# ESP8266.net
KiCad netlist of a schematic drawn in EAGLE
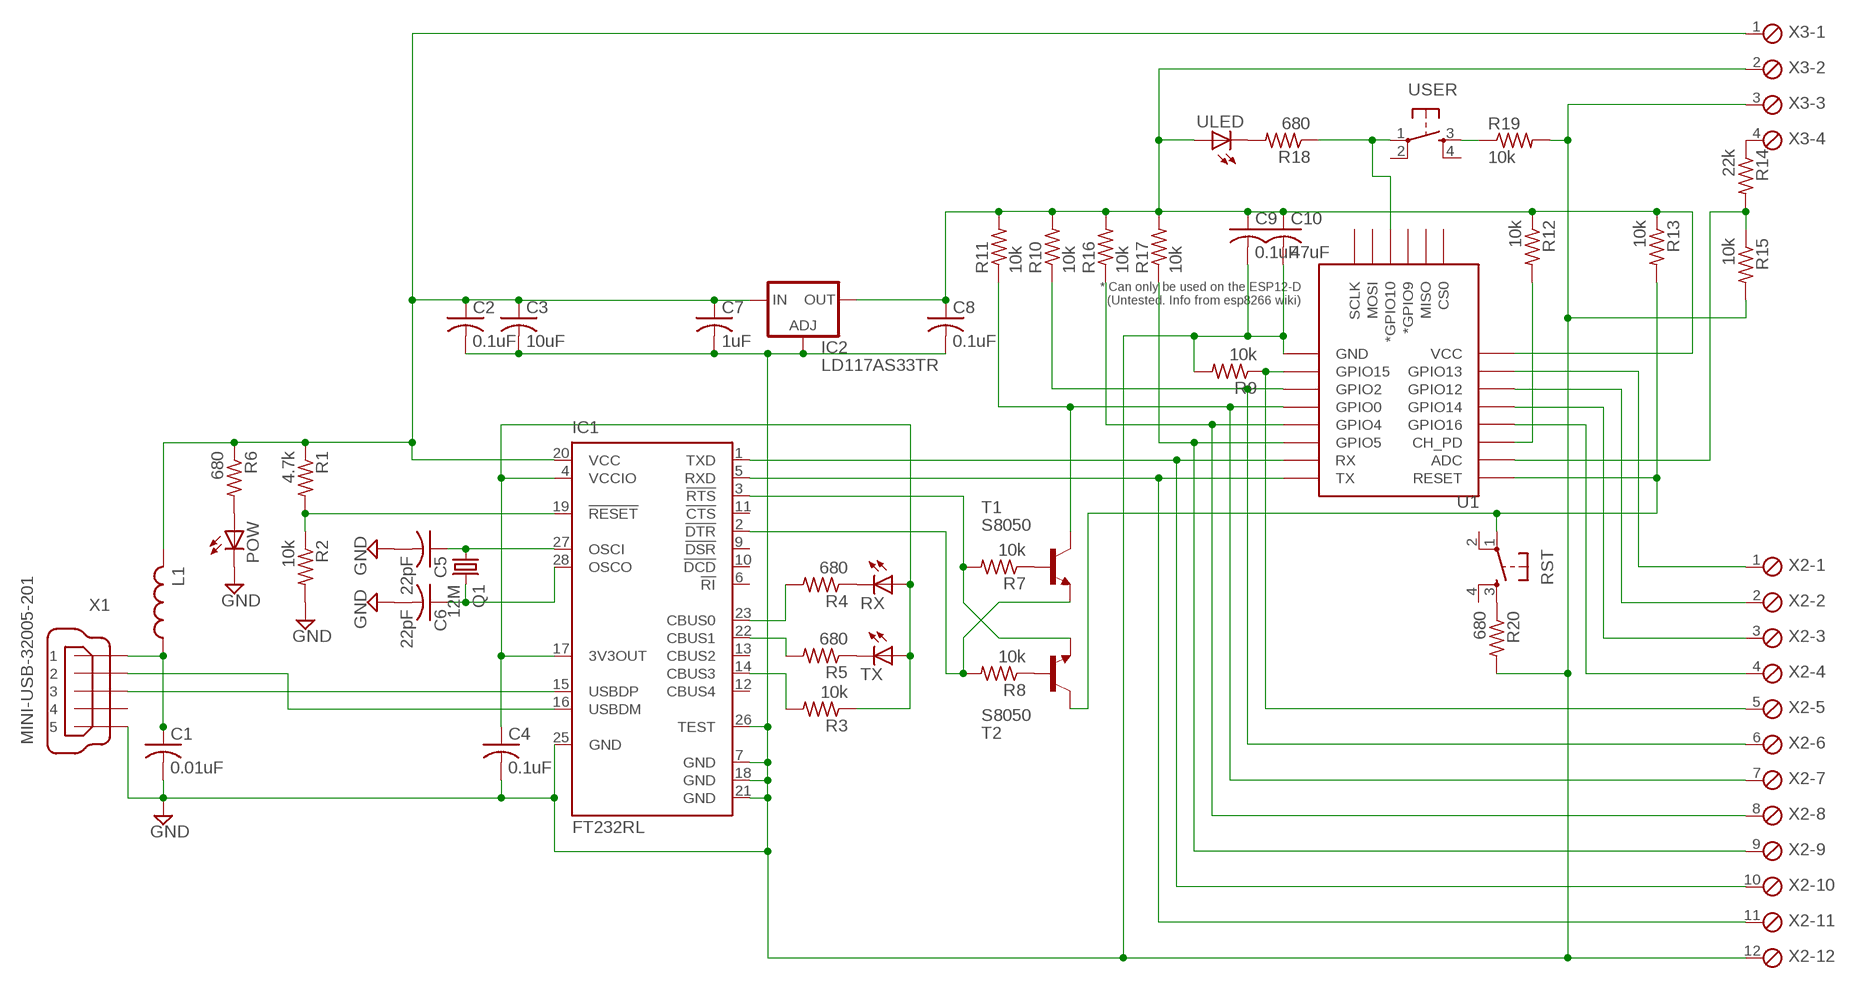
[diagram p0: schematic, sheet 1]

(export (version "E")
  (design (tool "Eeschema 10.0.6"))
  (components
    (comp (ref "C1")
      (value "0.01uF")
      (footprint "eagle-import:C0805")
      (libsource (lib "eagle-import") (part "C-USC0805"))
    )
    (comp (ref "C2")
      (value "0.1uF")
      (footprint "eagle-import:C0805")
      (libsource (lib "eagle-import") (part "C-USC0805"))
    )
    (comp (ref "C3")
      (value "10uF")
      (footprint "eagle-import:C0805")
      (libsource (lib "eagle-import") (part "C-USC0805"))
    )
    (comp (ref "C4")
      (value "0.1uF")
      (footprint "eagle-import:C0805")
      (libsource (lib "eagle-import") (part "C-USC0805"))
    )
    (comp (ref "C5")
      (value "22pF")
      (footprint "eagle-import:C0805")
      (libsource (lib "eagle-import") (part "C-USC0805"))
    )
    (comp (ref "C6")
      (value "22pF")
      (footprint "eagle-import:C0805")
      (libsource (lib "eagle-import") (part "C-USC0805"))
    )
    (comp (ref "C7")
      (value "1uF")
      (footprint "eagle-import:C0805")
      (libsource (lib "eagle-import") (part "C-USC0805"))
    )
    (comp (ref "C8")
      (value "0.1uF")
      (footprint "eagle-import:C0805")
      (libsource (lib "eagle-import") (part "C-USC0805"))
    )
    (comp (ref "C9")
      (value "0.1uF")
      (footprint "eagle-import:C0805")
      (libsource (lib "eagle-import") (part "C-USC0805"))
    )
    (comp (ref "C10")
      (value "47uF")
      (footprint "eagle-import:C0805")
      (libsource (lib "eagle-import") (part "C-USC0805"))
    )
    (comp (ref "IC1")
      (value "FT232RL")
      (footprint "eagle-import:SSOP28")
      (libsource (lib "eagle-import") (part "FT232RL"))
    )
    (comp (ref "IC2")
      (value "LD117AS33TR")
      (footprint "eagle-import:SOT223")
      (libsource (lib "eagle-import") (part "LD117A?S33TR"))
    )
    (comp (ref "L1")
      (value "L-USL2012C")
      (footprint "eagle-import:L2012C")
      (libsource (lib "eagle-import") (part "L-USL2012C"))
    )
    (comp (ref "POW")
      (value "LEDCHIP-LED0805")
      (footprint "eagle-import:CHIP-LED0805")
      (libsource (lib "eagle-import") (part "LEDCHIP-LED0805"))
    )
    (comp (ref "Q1")
      (value "12M")
      (footprint "eagle-import:SM49")
      (libsource (lib "eagle-import") (part "CRYSTALSM49"))
    )
    (comp (ref "R1")
      (value "4.7k")
      (footprint "eagle-import:R0805")
      (libsource (lib "eagle-import") (part "R-US_R0805"))
    )
    (comp (ref "R2")
      (value "10k")
      (footprint "eagle-import:R0805")
      (libsource (lib "eagle-import") (part "R-US_R0805"))
    )
    (comp (ref "R3")
      (value "10k")
      (footprint "eagle-import:R0805")
      (libsource (lib "eagle-import") (part "R-US_R0805"))
    )
    (comp (ref "R4")
      (value "680")
      (footprint "eagle-import:R0805")
      (libsource (lib "eagle-import") (part "R-US_R0805"))
    )
    (comp (ref "R5")
      (value "680")
      (footprint "eagle-import:R0805")
      (libsource (lib "eagle-import") (part "R-US_R0805"))
    )
    (comp (ref "R6")
      (value "680")
      (footprint "eagle-import:R0805")
      (libsource (lib "eagle-import") (part "R-US_R0805"))
    )
    (comp (ref "R7")
      (value "10k")
      (footprint "eagle-import:R0805")
      (libsource (lib "eagle-import") (part "R-US_R0805"))
    )
    (comp (ref "R8")
      (value "10k")
      (footprint "eagle-import:R0805")
      (libsource (lib "eagle-import") (part "R-US_R0805"))
    )
    (comp (ref "R9")
      (value "10k")
      (footprint "eagle-import:R0805")
      (libsource (lib "eagle-import") (part "R-US_R0805"))
    )
    (comp (ref "R10")
      (value "10k")
      (footprint "eagle-import:R0805")
      (libsource (lib "eagle-import") (part "R-US_R0805"))
    )
    (comp (ref "R11")
      (value "10k")
      (footprint "eagle-import:R0805")
      (libsource (lib "eagle-import") (part "R-US_R0805"))
    )
    (comp (ref "R12")
      (value "10k")
      (footprint "eagle-import:R0805")
      (libsource (lib "eagle-import") (part "R-US_R0805"))
    )
    (comp (ref "R13")
      (value "10k")
      (footprint "eagle-import:R0805")
      (libsource (lib "eagle-import") (part "R-US_R0805"))
    )
    (comp (ref "R14")
      (value "22k")
      (footprint "eagle-import:R0805")
      (libsource (lib "eagle-import") (part "R-US_R0805"))
    )
    (comp (ref "R15")
      (value "10k")
      (footprint "eagle-import:R0805")
      (libsource (lib "eagle-import") (part "R-US_R0805"))
    )
    (comp (ref "R16")
      (value "10k")
      (footprint "eagle-import:R0805")
      (libsource (lib "eagle-import") (part "R-US_R0805"))
    )
    (comp (ref "R17")
      (value "10k")
      (footprint "eagle-import:R0805")
      (libsource (lib "eagle-import") (part "R-US_R0805"))
    )
    (comp (ref "R18")
      (value "680")
      (footprint "eagle-import:R0805")
      (libsource (lib "eagle-import") (part "R-US_R0805"))
    )
    (comp (ref "R19")
      (value "10k")
      (footprint "eagle-import:R0805")
      (libsource (lib "eagle-import") (part "R-US_R0805"))
    )
    (comp (ref "R20")
      (value "680")
      (footprint "eagle-import:R0805")
      (libsource (lib "eagle-import") (part "R-US_R0805"))
    )
    (comp (ref "RST")
      (value "DTSM-6")
      (footprint "eagle-import:DTSM-6")
      (libsource (lib "eagle-import") (part "DTSM-6"))
    )
    (comp (ref "RX")
      (value "LEDCHIP-LED0805")
      (footprint "eagle-import:CHIP-LED0805")
      (libsource (lib "eagle-import") (part "LEDCHIP-LED0805"))
    )
    (comp (ref "T1")
      (value "S8050")
      (footprint "eagle-import:SOT23-EBC")
      (libsource (lib "eagle-import") (part "-NPN-SOT23-EBC"))
    )
    (comp (ref "T2")
      (value "S8050")
      (footprint "eagle-import:SOT23-EBC")
      (libsource (lib "eagle-import") (part "-NPN-SOT23-EBC"))
    )
    (comp (ref "TX")
      (value "LEDCHIP-LED0805")
      (footprint "eagle-import:CHIP-LED0805")
      (libsource (lib "eagle-import") (part "LEDCHIP-LED0805"))
    )
    (comp (ref "U1")
      (value "ESP12ESMD")
      (footprint "eagle-import:ESP12E-SMD")
      (libsource (lib "eagle-import") (part "ESP12ESMD"))
    )
    (comp (ref "ULED")
      (value "LEDCHIP-LED0805")
      (footprint "eagle-import:CHIP-LED0805")
      (libsource (lib "eagle-import") (part "LEDCHIP-LED0805"))
    )
    (comp (ref "USER")
      (value "DTSM-6")
      (footprint "eagle-import:DTSM-6")
      (libsource (lib "eagle-import") (part "DTSM-6"))
    )
    (comp (ref "X1")
      (value "MINI-USB-32005-201")
      (footprint "eagle-import:32005-201")
      (libsource (lib "eagle-import") (part "MINI-USB-32005-201"))
    )
    (comp (ref "X2")
      (value "MPT12")
      (footprint "eagle-import:12POL254")
      (libsource (lib "eagle-import") (part "MPT12"))
    )
    (comp (ref "X3")
      (value "MPT4")
      (footprint "eagle-import:4POL254")
      (libsource (lib "eagle-import") (part "MPT4"))
    )
  )
  (nets
    (net (code "1") (name "GND") (class "Default")
      (node (ref "C1") (pin "2") (pinfunction "2_2") (pintype "passive"))
      (node (ref "C10") (pin "2") (pinfunction "2_2") (pintype "passive"))
      (node (ref "C2") (pin "2") (pinfunction "2_2") (pintype "passive"))
      (node (ref "C3") (pin "2") (pinfunction "2_2") (pintype "passive"))
      (node (ref "C4") (pin "2") (pinfunction "2_2") (pintype "passive"))
      (node (ref "C5") (pin "2") (pinfunction "2_2") (pintype "passive"))
      (node (ref "C6") (pin "2") (pinfunction "2_2") (pintype "passive"))
      (node (ref "C7") (pin "2") (pinfunction "2_2") (pintype "passive"))
      (node (ref "C8") (pin "2") (pinfunction "2_2") (pintype "passive"))
      (node (ref "C9") (pin "2") (pinfunction "2_2") (pintype "passive"))
      (node (ref "IC1") (pin "18") (pinfunction "GND_18") (pintype "power_in"))
      (node (ref "IC1") (pin "21") (pinfunction "GND_21") (pintype "power_in"))
      (node (ref "IC1") (pin "25") (pinfunction "GND_25") (pintype "power_in"))
      (node (ref "IC1") (pin "26") (pinfunction "TEST_26") (pintype "input"))
      (node (ref "IC1") (pin "7") (pinfunction "GND_7") (pintype "power_in"))
      (node (ref "IC2") (pin "1") (pinfunction "ADJ_1") (pintype "input"))
      (node (ref "POW") (pin "C") (pinfunction "C_C") (pintype "passive"))
      (node (ref "R15") (pin "2") (pinfunction "2_2") (pintype "passive"))
      (node (ref "R19") (pin "2") (pinfunction "2_2") (pintype "passive"))
      (node (ref "R2") (pin "2") (pinfunction "2_2") (pintype "passive"))
      (node (ref "R20") (pin "2") (pinfunction "2_2") (pintype "passive"))
      (node (ref "R9") (pin "2") (pinfunction "2_2") (pintype "passive"))
      (node (ref "U1") (pin "GND") (pinfunction "GND_GND") (pintype "bidirectional"))
      (node (ref "X1") (pin "5") (pinfunction "5_5") (pintype "passive"))
      (node (ref "X2") (pin "12") (pinfunction "1_12") (pintype "passive"))
      (node (ref "X3") (pin "3") (pinfunction "1_3") (pintype "passive"))
    )
    (net (code "2") (name "Net-(C1-Pad1)") (class "Default")
      (node (ref "C1") (pin "1") (pinfunction "1_1") (pintype "passive"))
      (node (ref "L1") (pin "1") (pinfunction "1_1") (pintype "passive"))
      (node (ref "X1") (pin "1") (pinfunction "1_1") (pintype "passive"))
    )
    (net (code "3") (name "Net-(IC1-3V3OUT)") (class "Default")
      (node (ref "C4") (pin "1") (pinfunction "1_1") (pintype "passive"))
      (node (ref "IC1") (pin "17") (pinfunction "3V3OUT_17") (pintype "output"))
      (node (ref "IC1") (pin "4") (pinfunction "VCCIO_4") (pintype "power_in"))
      (node (ref "R3") (pin "1") (pinfunction "1_1") (pintype "passive"))
      (node (ref "RX") (pin "A") (pinfunction "A_A") (pintype "passive"))
      (node (ref "TX") (pin "A") (pinfunction "A_A") (pintype "passive"))
    )
    (net (code "4") (name "Net-(IC1-CBUS0)") (class "Default")
      (node (ref "IC1") (pin "23") (pinfunction "CBUS0_23") (pintype "bidirectional"))
      (node (ref "R4") (pin "2") (pinfunction "2_2") (pintype "passive"))
    )
    (net (code "5") (name "Net-(IC1-CBUS1)") (class "Default")
      (node (ref "IC1") (pin "22") (pinfunction "CBUS1_22") (pintype "bidirectional"))
      (node (ref "R5") (pin "2") (pinfunction "2_2") (pintype "passive"))
    )
    (net (code "6") (name "Net-(IC1-CBUS3)") (class "Default")
      (node (ref "IC1") (pin "14") (pinfunction "CBUS3_14") (pintype "bidirectional"))
      (node (ref "R3") (pin "2") (pinfunction "2_2") (pintype "passive"))
    )
    (net (code "7") (name "Net-(IC1-OSCI)") (class "Default")
      (node (ref "C5") (pin "1") (pinfunction "1_1") (pintype "passive"))
      (node (ref "IC1") (pin "27") (pinfunction "OSCI_27") (pintype "input"))
      (node (ref "Q1") (pin "1") (pinfunction "1_1") (pintype "passive"))
    )
    (net (code "8") (name "Net-(IC1-OSCO)") (class "Default")
      (node (ref "C6") (pin "1") (pinfunction "1_1") (pintype "passive"))
      (node (ref "IC1") (pin "28") (pinfunction "OSCO_28") (pintype "output"))
      (node (ref "Q1") (pin "2") (pinfunction "2_2") (pintype "passive"))
    )
    (net (code "9") (name "Net-(IC1-RXD)") (class "Default")
      (node (ref "IC1") (pin "5") (pinfunction "RXD_5") (pintype "input"))
      (node (ref "U1") (pin "TXD0") (pinfunction "TX_TXD0") (pintype "bidirectional"))
      (node (ref "X2") (pin "11") (pinfunction "1_11") (pintype "passive"))
    )
    (net (code "10") (name "Net-(IC1-TXD)") (class "Default")
      (node (ref "IC1") (pin "1") (pinfunction "TXD_1") (pintype "output"))
      (node (ref "U1") (pin "RXD0") (pinfunction "RX_RXD0") (pintype "bidirectional"))
      (node (ref "X2") (pin "10") (pinfunction "1_10") (pintype "passive"))
    )
    (net (code "11") (name "Net-(IC1-USBDM)") (class "Default")
      (node (ref "IC1") (pin "16") (pinfunction "USBDM_16") (pintype "bidirectional"))
      (node (ref "X1") (pin "2") (pinfunction "2_2") (pintype "passive"))
    )
    (net (code "12") (name "Net-(IC1-USBDP)") (class "Default")
      (node (ref "IC1") (pin "15") (pinfunction "USBDP_15") (pintype "bidirectional"))
      (node (ref "X1") (pin "3") (pinfunction "3_3") (pintype "passive"))
    )
    (net (code "13") (name "Net-(IC1-VCC)") (class "Default")
      (node (ref "C2") (pin "1") (pinfunction "1_1") (pintype "passive"))
      (node (ref "C3") (pin "1") (pinfunction "1_1") (pintype "passive"))
      (node (ref "C7") (pin "1") (pinfunction "1_1") (pintype "passive"))
      (node (ref "IC1") (pin "20") (pinfunction "VCC_20") (pintype "power_in"))
      (node (ref "IC2") (pin "3") (pinfunction "IN_3") (pintype "input"))
      (node (ref "L1") (pin "2") (pinfunction "2_2") (pintype "passive"))
      (node (ref "R1") (pin "1") (pinfunction "1_1") (pintype "passive"))
      (node (ref "R6") (pin "1") (pinfunction "1_1") (pintype "passive"))
      (node (ref "X3") (pin "1") (pinfunction "1_1") (pintype "passive"))
    )
    (net (code "14") (name "Net-(IC1-~{DTR})") (class "Default")
      (node (ref "IC1") (pin "2") (pinfunction "~{DTR}_2") (pintype "output"))
      (node (ref "R8") (pin "2") (pinfunction "2_2") (pintype "passive"))
      (node (ref "T1") (pin "E") (pinfunction "E_E") (pintype "passive"))
    )
    (net (code "15") (name "Net-(IC1-~{RESET})") (class "Default")
      (node (ref "IC1") (pin "19") (pinfunction "~{RESET}_19") (pintype "input"))
      (node (ref "R1") (pin "2") (pinfunction "2_2") (pintype "passive"))
      (node (ref "R2") (pin "1") (pinfunction "1_1") (pintype "passive"))
    )
    (net (code "16") (name "Net-(IC1-~{RTS})") (class "Default")
      (node (ref "IC1") (pin "3") (pinfunction "~{RTS}_3") (pintype "output"))
      (node (ref "R7") (pin "2") (pinfunction "2_2") (pintype "passive"))
      (node (ref "T2") (pin "E") (pinfunction "E_E") (pintype "passive"))
    )
    (net (code "17") (name "Net-(IC2-OUT)") (class "Default")
      (node (ref "C10") (pin "1") (pinfunction "1_1") (pintype "passive"))
      (node (ref "C8") (pin "1") (pinfunction "1_1") (pintype "passive"))
      (node (ref "C9") (pin "1") (pinfunction "1_1") (pintype "passive"))
      (node (ref "IC2") (pin "4") (pinfunction "OUT_4") (pintype "passive"))
      (node (ref "R10") (pin "2") (pinfunction "2_2") (pintype "passive"))
      (node (ref "R11") (pin "2") (pinfunction "2_2") (pintype "passive"))
      (node (ref "R12") (pin "1") (pinfunction "1_1") (pintype "passive"))
      (node (ref "R13") (pin "1") (pinfunction "1_1") (pintype "passive"))
      (node (ref "R16") (pin "2") (pinfunction "2_2") (pintype "passive"))
      (node (ref "R17") (pin "2") (pinfunction "2_2") (pintype "passive"))
      (node (ref "U1") (pin "VCC") (pinfunction "VCC_VCC") (pintype "bidirectional"))
      (node (ref "ULED") (pin "A") (pinfunction "A_A") (pintype "passive"))
      (node (ref "X3") (pin "2") (pinfunction "1_2") (pintype "passive"))
    )
    (net (code "18") (name "Net-(POW-PadA)") (class "Default")
      (node (ref "POW") (pin "A") (pinfunction "A_A") (pintype "passive"))
      (node (ref "R6") (pin "2") (pinfunction "2_2") (pintype "passive"))
    )
    (net (code "19") (name "Net-(R4-Pad1)") (class "Default")
      (node (ref "R4") (pin "1") (pinfunction "1_1") (pintype "passive"))
      (node (ref "RX") (pin "C") (pinfunction "C_C") (pintype "passive"))
    )
    (net (code "20") (name "Net-(R5-Pad1)") (class "Default")
      (node (ref "R5") (pin "1") (pinfunction "1_1") (pintype "passive"))
      (node (ref "TX") (pin "C") (pinfunction "C_C") (pintype "passive"))
    )
    (net (code "21") (name "Net-(R7-Pad1)") (class "Default")
      (node (ref "R7") (pin "1") (pinfunction "1_1") (pintype "passive"))
      (node (ref "T1") (pin "B") (pinfunction "B_B") (pintype "passive"))
    )
    (net (code "22") (name "Net-(R8-Pad1)") (class "Default")
      (node (ref "R8") (pin "1") (pinfunction "1_1") (pintype "passive"))
      (node (ref "T2") (pin "B") (pinfunction "B_B") (pintype "passive"))
    )
    (net (code "23") (name "Net-(R12-Pad2)") (class "Default")
      (node (ref "R12") (pin "2") (pinfunction "2_2") (pintype "passive"))
      (node (ref "U1") (pin "CH_PD") (pinfunction "CH_PD_CH_PD") (pintype "bidirectional"))
    )
    (net (code "24") (name "Net-(R13-Pad2)") (class "Default")
      (node (ref "R13") (pin "2") (pinfunction "2_2") (pintype "passive"))
      (node (ref "RST") (pin "1") (pinfunction "1_1") (pintype "passive"))
      (node (ref "T2") (pin "C") (pinfunction "C_C") (pintype "passive"))
      (node (ref "U1") (pin "RESET") (pinfunction "RESET_RESET") (pintype "bidirectional"))
    )
    (net (code "25") (name "Net-(R14-Pad2)") (class "Default")
      (node (ref "R14") (pin "2") (pinfunction "2_2") (pintype "passive"))
      (node (ref "R15") (pin "1") (pinfunction "1_1") (pintype "passive"))
      (node (ref "U1") (pin "ADC") (pinfunction "ADC_ADC") (pintype "bidirectional"))
    )
    (net (code "26") (name "Net-(R18-Pad2)") (class "Default")
      (node (ref "R18") (pin "2") (pinfunction "2_2") (pintype "passive"))
      (node (ref "ULED") (pin "C") (pinfunction "C_C") (pintype "passive"))
    )
    (net (code "27") (name "Net-(R19-Pad1)") (class "Default")
      (node (ref "R19") (pin "1") (pinfunction "1_1") (pintype "passive"))
      (node (ref "USER") (pin "3") (pinfunction "3_3") (pintype "passive"))
    )
    (net (code "28") (name "Net-(R20-Pad1)") (class "Default")
      (node (ref "R20") (pin "1") (pinfunction "1_1") (pintype "passive"))
      (node (ref "RST") (pin "3") (pinfunction "3_3") (pintype "passive"))
    )
    (net (code "29") (name "Net-(U1-*GPIO10)") (class "Default")
      (node (ref "R18") (pin "1") (pinfunction "1_1") (pintype "passive"))
      (node (ref "U1") (pin "GPIO10") (pinfunction "*GPIO10_GPIO10") (pintype "bidirectional"))
      (node (ref "USER") (pin "1") (pinfunction "1_1") (pintype "passive"))
    )
    (net (code "30") (name "Net-(U1-PadGPIO13)") (class "Default")
      (node (ref "U1") (pin "GPIO13") (pinfunction "GPIO13_GPIO13") (pintype "bidirectional"))
      (node (ref "X2") (pin "1") (pinfunction "1_1") (pintype "passive"))
    )
    (net (code "31") (name "Net-(X2E-1)") (class "Default")
      (node (ref "U1") (pin "GPIO12") (pinfunction "GPIO12_GPIO12") (pintype "bidirectional"))
      (node (ref "X2") (pin "2") (pinfunction "1_2") (pintype "passive"))
    )
    (net (code "32") (name "Net-(X2F-1)") (class "Default")
      (node (ref "U1") (pin "GPIO14") (pinfunction "GPIO14_GPIO14") (pintype "bidirectional"))
      (node (ref "X2") (pin "3") (pinfunction "1_3") (pintype "passive"))
    )
    (net (code "33") (name "Net-(X2G-1)") (class "Default")
      (node (ref "U1") (pin "GPIO16") (pinfunction "GPIO16_GPIO16") (pintype "bidirectional"))
      (node (ref "X2") (pin "4") (pinfunction "1_4") (pintype "passive"))
    )
    (net (code "34") (name "Net-(X2H-1)") (class "Default")
      (node (ref "R9") (pin "1") (pinfunction "1_1") (pintype "passive"))
      (node (ref "U1") (pin "GPIO15") (pinfunction "GPIO15_GPIO15") (pintype "bidirectional"))
      (node (ref "X2") (pin "5") (pinfunction "1_5") (pintype "passive"))
    )
    (net (code "35") (name "Net-(X2I-1)") (class "Default")
      (node (ref "R10") (pin "1") (pinfunction "1_1") (pintype "passive"))
      (node (ref "U1") (pin "GPIO2") (pinfunction "GPIO2_GPIO2") (pintype "bidirectional"))
      (node (ref "X2") (pin "6") (pinfunction "1_6") (pintype "passive"))
    )
    (net (code "36") (name "Net-(X2J-1)") (class "Default")
      (node (ref "R11") (pin "1") (pinfunction "1_1") (pintype "passive"))
      (node (ref "T1") (pin "C") (pinfunction "C_C") (pintype "passive"))
      (node (ref "U1") (pin "GPIO0") (pinfunction "GPIO0_GPIO0") (pintype "bidirectional"))
      (node (ref "X2") (pin "7") (pinfunction "1_7") (pintype "passive"))
    )
    (net (code "37") (name "Net-(X2K-1)") (class "Default")
      (node (ref "R16") (pin "1") (pinfunction "1_1") (pintype "passive"))
      (node (ref "U1") (pin "GPIO4") (pinfunction "GPIO4_GPIO4") (pintype "bidirectional"))
      (node (ref "X2") (pin "8") (pinfunction "1_8") (pintype "passive"))
    )
    (net (code "38") (name "Net-(X2L-1)") (class "Default")
      (node (ref "R17") (pin "1") (pinfunction "1_1") (pintype "passive"))
      (node (ref "U1") (pin "GPIO5") (pinfunction "GPIO5_GPIO5") (pintype "bidirectional"))
      (node (ref "X2") (pin "9") (pinfunction "1_9") (pintype "passive"))
    )
    (net (code "39") (name "Net-(X3D-1)") (class "Default")
      (node (ref "R14") (pin "1") (pinfunction "1_1") (pintype "passive"))
      (node (ref "X3") (pin "4") (pinfunction "1_4") (pintype "passive"))
    )
    (net (code "40") (name "unconnected-(IC1-CBUS2-Pad13)") (class "Default")
      (node (ref "IC1") (pin "13") (pinfunction "CBUS2_13") (pintype "bidirectional"))
    )
    (net (code "41") (name "unconnected-(IC1-CBUS4-Pad12)") (class "Default")
      (node (ref "IC1") (pin "12") (pinfunction "CBUS4_12") (pintype "bidirectional"))
    )
    (net (code "42") (name "unconnected-(IC1-~{CTS}-Pad11)") (class "Default")
      (node (ref "IC1") (pin "11") (pinfunction "~{CTS}_11") (pintype "input"))
    )
    (net (code "43") (name "unconnected-(IC1-~{DCD}-Pad10)") (class "Default")
      (node (ref "IC1") (pin "10") (pinfunction "~{DCD}_10") (pintype "input"))
    )
    (net (code "44") (name "unconnected-(IC1-~{DSR}-Pad9)") (class "Default")
      (node (ref "IC1") (pin "9") (pinfunction "~{DSR}_9") (pintype "input"))
    )
    (net (code "45") (name "unconnected-(IC1-~{RI}-Pad6)") (class "Default")
      (node (ref "IC1") (pin "6") (pinfunction "~{RI}_6") (pintype "input"))
    )
    (net (code "46") (name "unconnected-(RST-Pad2)") (class "Default")
      (node (ref "RST") (pin "2") (pinfunction "2_2") (pintype "passive"))
    )
    (net (code "47") (name "unconnected-(RST-Pad4)") (class "Default")
      (node (ref "RST") (pin "4") (pinfunction "4_4") (pintype "passive"))
    )
    (net (code "48") (name "unconnected-(U1-*GPIO9-PadGPIO9)") (class "Default")
      (node (ref "U1") (pin "GPIO9") (pinfunction "*GPIO9_GPIO9") (pintype "bidirectional"))
    )
    (net (code "49") (name "unconnected-(U1-PadCS0)") (class "Default")
      (node (ref "U1") (pin "CS0") (pinfunction "CS0_CS0") (pintype "bidirectional"))
    )
    (net (code "50") (name "unconnected-(U1-PadMISO)") (class "Default")
      (node (ref "U1") (pin "MISO") (pinfunction "MISO_MISO") (pintype "bidirectional"))
    )
    (net (code "51") (name "unconnected-(U1-PadMOSI)") (class "Default")
      (node (ref "U1") (pin "MOSI") (pinfunction "MOSI_MOSI") (pintype "bidirectional"))
    )
    (net (code "52") (name "unconnected-(U1-PadSCLK)") (class "Default")
      (node (ref "U1") (pin "SCLK") (pinfunction "SCLK_SCLK") (pintype "bidirectional"))
    )
    (net (code "53") (name "unconnected-(USER-Pad2)") (class "Default")
      (node (ref "USER") (pin "2") (pinfunction "2_2") (pintype "passive"))
    )
    (net (code "54") (name "unconnected-(USER-Pad4)") (class "Default")
      (node (ref "USER") (pin "4") (pinfunction "4_4") (pintype "passive"))
    )
    (net (code "55") (name "unconnected-(X1-Pad4)") (class "Default")
      (node (ref "X1") (pin "4") (pinfunction "4_4") (pintype "passive"))
    )
  )
)
